# main_schematic.net
KiCad netlist of a schematic drawn in Altium Designer
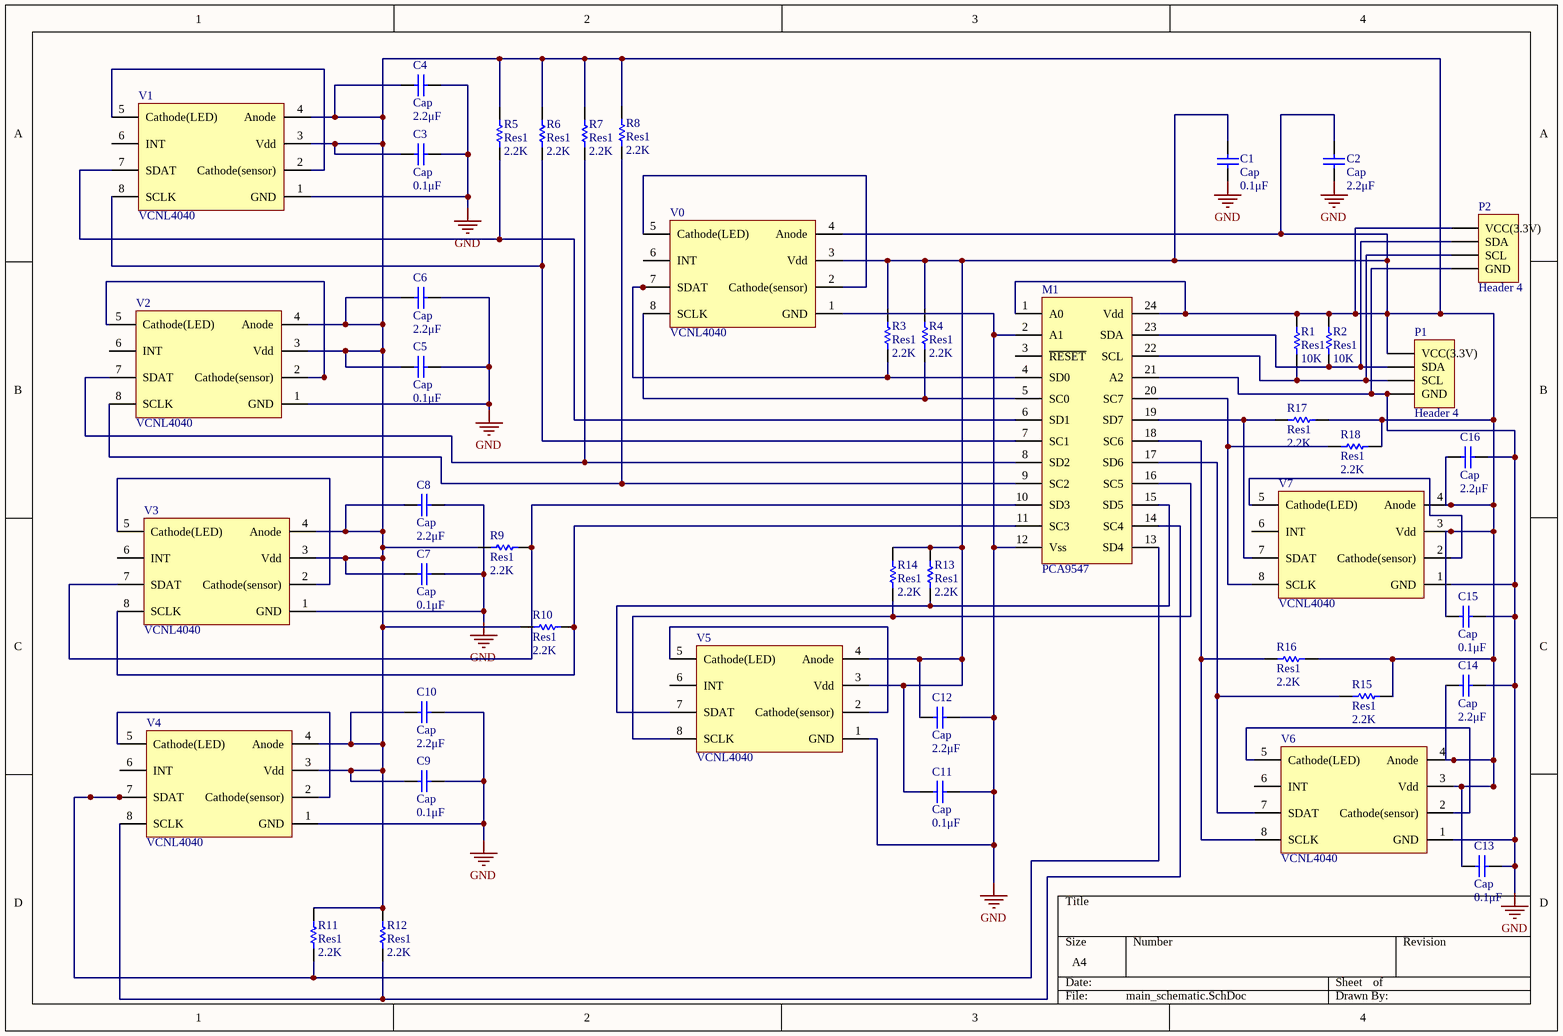
[diagram p0: main_schematic.SchDoc]

(export (version "E")
  (design (tool "Eeschema 10.0.6"))
  (components
    (comp (ref "C1")
      (value "Cap")
      (footprint "1608[0603]")
      (description "Capacitor")
      (fields (field (name "ALTIUM_VALUE") "0.1μF") (field (name "PUBLISHER") "Altium Limited"))
      (libsource (lib "Miscellaneous Devices") (part "Cap"))
    )
    (comp (ref "C2")
      (value "Cap")
      (footprint "1608[0603]")
      (description "Capacitor")
      (fields (field (name "ALTIUM_VALUE") "2.2μF") (field (name "PUBLISHER") "Altium Limited"))
      (libsource (lib "Miscellaneous Devices") (part "Cap"))
    )
    (comp (ref "C3")
      (value "Cap")
      (footprint "1608[0603]")
      (description "Capacitor")
      (fields (field (name "ALTIUM_VALUE") "0.1μF") (field (name "PUBLISHER") "Altium Limited"))
      (libsource (lib "Miscellaneous Devices") (part "Cap"))
    )
    (comp (ref "C4")
      (value "Cap")
      (footprint "1608[0603]")
      (description "Capacitor")
      (fields (field (name "ALTIUM_VALUE") "2.2μF") (field (name "PUBLISHER") "Altium Limited"))
      (libsource (lib "Miscellaneous Devices") (part "Cap"))
    )
    (comp (ref "C5")
      (value "Cap")
      (footprint "1608[0603]")
      (description "Capacitor")
      (fields (field (name "ALTIUM_VALUE") "0.1μF") (field (name "PUBLISHER") "Altium Limited"))
      (libsource (lib "Miscellaneous Devices") (part "Cap"))
    )
    (comp (ref "C6")
      (value "Cap")
      (footprint "1608[0603]")
      (description "Capacitor")
      (fields (field (name "ALTIUM_VALUE") "2.2μF") (field (name "PUBLISHER") "Altium Limited"))
      (libsource (lib "Miscellaneous Devices") (part "Cap"))
    )
    (comp (ref "C7")
      (value "Cap")
      (footprint "1608[0603]")
      (description "Capacitor")
      (fields (field (name "ALTIUM_VALUE") "0.1μF") (field (name "PUBLISHER") "Altium Limited"))
      (libsource (lib "Miscellaneous Devices") (part "Cap"))
    )
    (comp (ref "C8")
      (value "Cap")
      (footprint "1608[0603]")
      (description "Capacitor")
      (fields (field (name "ALTIUM_VALUE") "2.2μF") (field (name "PUBLISHER") "Altium Limited"))
      (libsource (lib "Miscellaneous Devices") (part "Cap"))
    )
    (comp (ref "C9")
      (value "Cap")
      (footprint "1608[0603]")
      (description "Capacitor")
      (fields (field (name "ALTIUM_VALUE") "0.1μF") (field (name "PUBLISHER") "Altium Limited"))
      (libsource (lib "Miscellaneous Devices") (part "Cap"))
    )
    (comp (ref "C10")
      (value "Cap")
      (footprint "1608[0603]")
      (description "Capacitor")
      (fields (field (name "ALTIUM_VALUE") "2.2μF") (field (name "PUBLISHER") "Altium Limited"))
      (libsource (lib "Miscellaneous Devices") (part "Cap"))
    )
    (comp (ref "C11")
      (value "Cap")
      (footprint "1608[0603]")
      (description "Capacitor")
      (fields (field (name "ALTIUM_VALUE") "0.1μF") (field (name "PUBLISHER") "Altium Limited"))
      (libsource (lib "Miscellaneous Devices") (part "Cap"))
    )
    (comp (ref "C12")
      (value "Cap")
      (footprint "1608[0603]")
      (description "Capacitor")
      (fields (field (name "ALTIUM_VALUE") "2.2μF") (field (name "PUBLISHER") "Altium Limited"))
      (libsource (lib "Miscellaneous Devices") (part "Cap"))
    )
    (comp (ref "C13")
      (value "Cap")
      (footprint "1608[0603]")
      (description "Capacitor")
      (fields (field (name "ALTIUM_VALUE") "0.1μF") (field (name "PUBLISHER") "Altium Limited"))
      (libsource (lib "Miscellaneous Devices") (part "Cap"))
    )
    (comp (ref "C14")
      (value "Cap")
      (footprint "1608[0603]")
      (description "Capacitor")
      (fields (field (name "ALTIUM_VALUE") "2.2μF") (field (name "PUBLISHER") "Altium Limited"))
      (libsource (lib "Miscellaneous Devices") (part "Cap"))
    )
    (comp (ref "C15")
      (value "Cap")
      (footprint "1608[0603]")
      (description "Capacitor")
      (fields (field (name "ALTIUM_VALUE") "0.1μF") (field (name "PUBLISHER") "Altium Limited"))
      (libsource (lib "Miscellaneous Devices") (part "Cap"))
    )
    (comp (ref "C16")
      (value "Cap")
      (footprint "1608[0603]")
      (description "Capacitor")
      (fields (field (name "ALTIUM_VALUE") "2.2μF") (field (name "PUBLISHER") "Altium Limited"))
      (libsource (lib "Miscellaneous Devices") (part "Cap"))
    )
    (comp (ref "M1") (value "PCA9547") (footprint "TSSOP24") (libsource (lib "PCA9547") (part "PCA9547")))
    (comp (ref "P1")
      (value "Header 4")
      (footprint "HDR1X4")
      (description "Header, 4-Pin")
      (fields (field (name "PUBLISHER") "Altium Limited"))
      (libsource (lib "Miscellaneous Connectors") (part "Header 4"))
    )
    (comp (ref "P2")
      (value "Header 4")
      (footprint "HDR1X4")
      (description "Header, 4-Pin")
      (fields (field (name "PUBLISHER") "Altium Limited"))
      (libsource (lib "Miscellaneous Connectors") (part "Header 4"))
    )
    (comp (ref "R1")
      (value "Res1")
      (footprint "1608[0603]")
      (description "Resistor")
      (fields (field (name "ALTIUM_VALUE") "10K") (field (name "PUBLISHER") "Altium Limited"))
      (libsource (lib "Miscellaneous Devices") (part "Res1"))
    )
    (comp (ref "R2")
      (value "Res1")
      (footprint "1608[0603]")
      (description "Resistor")
      (fields (field (name "ALTIUM_VALUE") "10K") (field (name "PUBLISHER") "Altium Limited"))
      (libsource (lib "Miscellaneous Devices") (part "Res1"))
    )
    (comp (ref "R3")
      (value "Res1")
      (footprint "1608[0603]")
      (description "Resistor")
      (fields (field (name "ALTIUM_VALUE") "2.2K") (field (name "PUBLISHER") "Altium Limited"))
      (libsource (lib "Miscellaneous Devices") (part "Res1"))
    )
    (comp (ref "R4")
      (value "Res1")
      (footprint "1608[0603]")
      (description "Resistor")
      (fields (field (name "ALTIUM_VALUE") "2.2K") (field (name "PUBLISHER") "Altium Limited"))
      (libsource (lib "Miscellaneous Devices") (part "Res1"))
    )
    (comp (ref "R5")
      (value "Res1")
      (footprint "1608[0603]")
      (description "Resistor")
      (fields (field (name "ALTIUM_VALUE") "2.2K") (field (name "PUBLISHER") "Altium Limited"))
      (libsource (lib "Miscellaneous Devices") (part "Res1"))
    )
    (comp (ref "R6")
      (value "Res1")
      (footprint "1608[0603]")
      (description "Resistor")
      (fields (field (name "ALTIUM_VALUE") "2.2K") (field (name "PUBLISHER") "Altium Limited"))
      (libsource (lib "Miscellaneous Devices") (part "Res1"))
    )
    (comp (ref "R7")
      (value "Res1")
      (footprint "1608[0603]")
      (description "Resistor")
      (fields (field (name "ALTIUM_VALUE") "2.2K") (field (name "PUBLISHER") "Altium Limited"))
      (libsource (lib "Miscellaneous Devices") (part "Res1"))
    )
    (comp (ref "R8")
      (value "Res1")
      (footprint "1608[0603]")
      (description "Resistor")
      (fields (field (name "ALTIUM_VALUE") "2.2K") (field (name "PUBLISHER") "Altium Limited"))
      (libsource (lib "Miscellaneous Devices") (part "Res1"))
    )
    (comp (ref "R9")
      (value "Res1")
      (footprint "1608[0603]")
      (description "Resistor")
      (fields (field (name "ALTIUM_VALUE") "2.2K") (field (name "PUBLISHER") "Altium Limited"))
      (libsource (lib "Miscellaneous Devices") (part "Res1"))
    )
    (comp (ref "R10")
      (value "Res1")
      (footprint "1608[0603]")
      (description "Resistor")
      (fields (field (name "ALTIUM_VALUE") "2.2K") (field (name "PUBLISHER") "Altium Limited"))
      (libsource (lib "Miscellaneous Devices") (part "Res1"))
    )
    (comp (ref "R11")
      (value "Res1")
      (footprint "1608[0603]")
      (description "Resistor")
      (fields (field (name "ALTIUM_VALUE") "2.2K") (field (name "PUBLISHER") "Altium Limited"))
      (libsource (lib "Miscellaneous Devices") (part "Res1"))
    )
    (comp (ref "R12")
      (value "Res1")
      (footprint "1608[0603]")
      (description "Resistor")
      (fields (field (name "ALTIUM_VALUE") "2.2K") (field (name "PUBLISHER") "Altium Limited"))
      (libsource (lib "Miscellaneous Devices") (part "Res1"))
    )
    (comp (ref "R13")
      (value "Res1")
      (footprint "1608[0603]")
      (description "Resistor")
      (fields (field (name "ALTIUM_VALUE") "2.2K") (field (name "PUBLISHER") "Altium Limited"))
      (libsource (lib "Miscellaneous Devices") (part "Res1"))
    )
    (comp (ref "R14")
      (value "Res1")
      (footprint "1608[0603]")
      (description "Resistor")
      (fields (field (name "ALTIUM_VALUE") "2.2K") (field (name "PUBLISHER") "Altium Limited"))
      (libsource (lib "Miscellaneous Devices") (part "Res1"))
    )
    (comp (ref "R15")
      (value "Res1")
      (footprint "1608[0603]")
      (description "Resistor")
      (fields (field (name "ALTIUM_VALUE") "2.2K") (field (name "PUBLISHER") "Altium Limited"))
      (libsource (lib "Miscellaneous Devices") (part "Res1"))
    )
    (comp (ref "R16")
      (value "Res1")
      (footprint "1608[0603]")
      (description "Resistor")
      (fields (field (name "ALTIUM_VALUE") "2.2K") (field (name "PUBLISHER") "Altium Limited"))
      (libsource (lib "Miscellaneous Devices") (part "Res1"))
    )
    (comp (ref "R17")
      (value "Res1")
      (footprint "1608[0603]")
      (description "Resistor")
      (fields (field (name "ALTIUM_VALUE") "2.2K") (field (name "PUBLISHER") "Altium Limited"))
      (libsource (lib "Miscellaneous Devices") (part "Res1"))
    )
    (comp (ref "R18")
      (value "Res1")
      (footprint "1608[0603]")
      (description "Resistor")
      (fields (field (name "ALTIUM_VALUE") "2.2K") (field (name "PUBLISHER") "Altium Limited"))
      (libsource (lib "Miscellaneous Devices") (part "Res1"))
    )
    (comp (ref "V0") (value "VCNL4040") (footprint "SOP8") (libsource (lib "VCNL4040") (part "Component_1")))
    (comp (ref "V1") (value "VCNL4040") (footprint "SOP8") (libsource (lib "VCNL4040") (part "Component_1")))
    (comp (ref "V2") (value "VCNL4040") (footprint "SOP8") (libsource (lib "VCNL4040") (part "Component_1")))
    (comp (ref "V3") (value "VCNL4040") (footprint "SOP8") (libsource (lib "VCNL4040") (part "Component_1")))
    (comp (ref "V4") (value "VCNL4040") (footprint "SOP8") (libsource (lib "VCNL4040") (part "Component_1")))
    (comp (ref "V5") (value "VCNL4040") (footprint "SOP8") (libsource (lib "VCNL4040") (part "Component_1")))
    (comp (ref "V6") (value "VCNL4040") (footprint "SOP8") (libsource (lib "VCNL4040") (part "Component_1")))
    (comp (ref "V7") (value "VCNL4040") (footprint "SOP8") (libsource (lib "VCNL4040") (part "Component_1")))
  )
  (nets
    (net (code "1") (name "GND") (class "Default")
      (node (ref "C1") (pin "1") (pinfunction "1_1") (pintype "passive"))
      (node (ref "C10") (pin "1") (pinfunction "1_1") (pintype "passive"))
      (node (ref "C11") (pin "1") (pinfunction "1_1") (pintype "passive"))
      (node (ref "C12") (pin "1") (pinfunction "1_1") (pintype "passive"))
      (node (ref "C13") (pin "1") (pinfunction "1_1") (pintype "passive"))
      (node (ref "C14") (pin "1") (pinfunction "1_1") (pintype "passive"))
      (node (ref "C15") (pin "1") (pinfunction "1_1") (pintype "passive"))
      (node (ref "C16") (pin "1") (pinfunction "1_1") (pintype "passive"))
      (node (ref "C2") (pin "1") (pinfunction "1_1") (pintype "passive"))
      (node (ref "C3") (pin "1") (pinfunction "1_1") (pintype "passive"))
      (node (ref "C4") (pin "1") (pinfunction "1_1") (pintype "passive"))
      (node (ref "C5") (pin "1") (pinfunction "1_1") (pintype "passive"))
      (node (ref "C6") (pin "1") (pinfunction "1_1") (pintype "passive"))
      (node (ref "C7") (pin "1") (pinfunction "1_1") (pintype "passive"))
      (node (ref "C8") (pin "1") (pinfunction "1_1") (pintype "passive"))
      (node (ref "C9") (pin "1") (pinfunction "1_1") (pintype "passive"))
      (node (ref "M1") (pin "12") (pinfunction "Vss_12") (pintype "passive"))
      (node (ref "M1") (pin "2") (pinfunction "A1_2") (pintype "passive"))
      (node (ref "M1") (pin "21") (pinfunction "A2_21") (pintype "passive"))
      (node (ref "P1") (pin "4") (pinfunction "GND_4") (pintype "passive"))
      (node (ref "P2") (pin "4") (pinfunction "GND_4") (pintype "passive"))
      (node (ref "V0") (pin "1") (pinfunction "GND_1") (pintype "passive"))
      (node (ref "V1") (pin "1") (pinfunction "GND_1") (pintype "passive"))
      (node (ref "V2") (pin "1") (pinfunction "GND_1") (pintype "passive"))
      (node (ref "V3") (pin "1") (pinfunction "GND_1") (pintype "passive"))
      (node (ref "V4") (pin "1") (pinfunction "GND_1") (pintype "passive"))
      (node (ref "V5") (pin "1") (pinfunction "GND_1") (pintype "passive"))
      (node (ref "V6") (pin "1") (pinfunction "GND_1") (pintype "passive"))
      (node (ref "V7") (pin "1") (pinfunction "GND_1") (pintype "passive"))
    )
    (net (code "2") (name "Net-(M1-A0)") (class "Default")
      (node (ref "C1") (pin "2") (pinfunction "2_2") (pintype "passive"))
      (node (ref "C10") (pin "2") (pinfunction "2_2") (pintype "passive"))
      (node (ref "C11") (pin "2") (pinfunction "2_2") (pintype "passive"))
      (node (ref "C12") (pin "2") (pinfunction "2_2") (pintype "passive"))
      (node (ref "C13") (pin "2") (pinfunction "2_2") (pintype "passive"))
      (node (ref "C14") (pin "2") (pinfunction "2_2") (pintype "passive"))
      (node (ref "C15") (pin "2") (pinfunction "2_2") (pintype "passive"))
      (node (ref "C16") (pin "2") (pinfunction "2_2") (pintype "passive"))
      (node (ref "C2") (pin "2") (pinfunction "2_2") (pintype "passive"))
      (node (ref "C3") (pin "2") (pinfunction "2_2") (pintype "passive"))
      (node (ref "C4") (pin "2") (pinfunction "2_2") (pintype "passive"))
      (node (ref "C5") (pin "2") (pinfunction "2_2") (pintype "passive"))
      (node (ref "C6") (pin "2") (pinfunction "2_2") (pintype "passive"))
      (node (ref "C7") (pin "2") (pinfunction "2_2") (pintype "passive"))
      (node (ref "C8") (pin "2") (pinfunction "2_2") (pintype "passive"))
      (node (ref "C9") (pin "2") (pinfunction "2_2") (pintype "passive"))
      (node (ref "M1") (pin "1") (pinfunction "A0_1") (pintype "passive"))
      (node (ref "M1") (pin "24") (pinfunction "Vdd_24") (pintype "passive"))
      (node (ref "P1") (pin "1") (pinfunction "VCC(3.3V)_1") (pintype "passive"))
      (node (ref "P2") (pin "1") (pinfunction "VCC(3.3V)_1") (pintype "passive"))
      (node (ref "R1") (pin "2") (pinfunction "2_2") (pintype "passive"))
      (node (ref "R10") (pin "2") (pinfunction "2_2") (pintype "passive"))
      (node (ref "R11") (pin "1") (pinfunction "1_1") (pintype "passive"))
      (node (ref "R12") (pin "1") (pinfunction "1_1") (pintype "passive"))
      (node (ref "R13") (pin "2") (pinfunction "2_2") (pintype "passive"))
      (node (ref "R14") (pin "2") (pinfunction "2_2") (pintype "passive"))
      (node (ref "R15") (pin "1") (pinfunction "1_1") (pintype "passive"))
      (node (ref "R16") (pin "1") (pinfunction "1_1") (pintype "passive"))
      (node (ref "R17") (pin "1") (pinfunction "1_1") (pintype "passive"))
      (node (ref "R18") (pin "1") (pinfunction "1_1") (pintype "passive"))
      (node (ref "R2") (pin "2") (pinfunction "2_2") (pintype "passive"))
      (node (ref "R3") (pin "2") (pinfunction "2_2") (pintype "passive"))
      (node (ref "R4") (pin "2") (pinfunction "2_2") (pintype "passive"))
      (node (ref "R5") (pin "2") (pinfunction "2_2") (pintype "passive"))
      (node (ref "R6") (pin "2") (pinfunction "2_2") (pintype "passive"))
      (node (ref "R7") (pin "2") (pinfunction "2_2") (pintype "passive"))
      (node (ref "R8") (pin "2") (pinfunction "2_2") (pintype "passive"))
      (node (ref "R9") (pin "2") (pinfunction "2_2") (pintype "passive"))
      (node (ref "V0") (pin "3") (pinfunction "Vdd_3") (pintype "passive"))
      (node (ref "V0") (pin "4") (pinfunction "Anode_4") (pintype "passive"))
      (node (ref "V1") (pin "3") (pinfunction "Vdd_3") (pintype "passive"))
      (node (ref "V1") (pin "4") (pinfunction "Anode_4") (pintype "passive"))
      (node (ref "V2") (pin "3") (pinfunction "Vdd_3") (pintype "passive"))
      (node (ref "V2") (pin "4") (pinfunction "Anode_4") (pintype "passive"))
      (node (ref "V3") (pin "3") (pinfunction "Vdd_3") (pintype "passive"))
      (node (ref "V3") (pin "4") (pinfunction "Anode_4") (pintype "passive"))
      (node (ref "V4") (pin "3") (pinfunction "Vdd_3") (pintype "passive"))
      (node (ref "V4") (pin "4") (pinfunction "Anode_4") (pintype "passive"))
      (node (ref "V5") (pin "3") (pinfunction "Vdd_3") (pintype "passive"))
      (node (ref "V5") (pin "4") (pinfunction "Anode_4") (pintype "passive"))
      (node (ref "V6") (pin "3") (pinfunction "Vdd_3") (pintype "passive"))
      (node (ref "V6") (pin "4") (pinfunction "Anode_4") (pintype "passive"))
      (node (ref "V7") (pin "3") (pinfunction "Vdd_3") (pintype "passive"))
      (node (ref "V7") (pin "4") (pinfunction "Anode_4") (pintype "passive"))
    )
    (net (code "3") (name "Net-(M1-SC0)") (class "Default")
      (node (ref "M1") (pin "5") (pinfunction "SC0_5") (pintype "passive"))
      (node (ref "R4") (pin "1") (pinfunction "1_1") (pintype "passive"))
      (node (ref "V0") (pin "8") (pinfunction "SCLK_8") (pintype "passive"))
    )
    (net (code "4") (name "Net-(M1-SC1)") (class "Default")
      (node (ref "M1") (pin "7") (pinfunction "SC1_7") (pintype "passive"))
      (node (ref "R6") (pin "1") (pinfunction "1_1") (pintype "passive"))
      (node (ref "V1") (pin "8") (pinfunction "SCLK_8") (pintype "passive"))
    )
    (net (code "5") (name "Net-(M1-SC2)") (class "Default")
      (node (ref "M1") (pin "9") (pinfunction "SC2_9") (pintype "passive"))
      (node (ref "R8") (pin "1") (pinfunction "1_1") (pintype "passive"))
      (node (ref "V2") (pin "8") (pinfunction "SCLK_8") (pintype "passive"))
    )
    (net (code "6") (name "Net-(M1-SC3)") (class "Default")
      (node (ref "M1") (pin "11") (pinfunction "SC3_11") (pintype "passive"))
      (node (ref "R10") (pin "1") (pinfunction "1_1") (pintype "passive"))
      (node (ref "V3") (pin "8") (pinfunction "SCLK_8") (pintype "passive"))
    )
    (net (code "7") (name "Net-(M1-SC4)") (class "Default")
      (node (ref "M1") (pin "14") (pinfunction "SC4_14") (pintype "passive"))
      (node (ref "R12") (pin "2") (pinfunction "2_2") (pintype "passive"))
      (node (ref "V4") (pin "8") (pinfunction "SCLK_8") (pintype "passive"))
    )
    (net (code "8") (name "Net-(M1-SC5)") (class "Default")
      (node (ref "M1") (pin "16") (pinfunction "SC5_16") (pintype "passive"))
      (node (ref "R14") (pin "1") (pinfunction "1_1") (pintype "passive"))
      (node (ref "V5") (pin "8") (pinfunction "SCLK_8") (pintype "passive"))
    )
    (net (code "9") (name "Net-(M1-SC6)") (class "Default")
      (node (ref "M1") (pin "18") (pinfunction "SC6_18") (pintype "passive"))
      (node (ref "R16") (pin "2") (pinfunction "2_2") (pintype "passive"))
      (node (ref "V6") (pin "8") (pinfunction "SCLK_8") (pintype "passive"))
    )
    (net (code "10") (name "Net-(M1-SC7)") (class "Default")
      (node (ref "M1") (pin "20") (pinfunction "SC7_20") (pintype "passive"))
      (node (ref "R18") (pin "2") (pinfunction "2_2") (pintype "passive"))
      (node (ref "V7") (pin "8") (pinfunction "SCLK_8") (pintype "passive"))
    )
    (net (code "11") (name "Net-(M1-SCL)") (class "Default")
      (node (ref "M1") (pin "22") (pinfunction "SCL_22") (pintype "passive"))
      (node (ref "P1") (pin "3") (pinfunction "SCL_3") (pintype "passive"))
      (node (ref "P2") (pin "3") (pinfunction "SCL_3") (pintype "passive"))
      (node (ref "R1") (pin "1") (pinfunction "1_1") (pintype "passive"))
    )
    (net (code "12") (name "Net-(M1-SD0)") (class "Default")
      (node (ref "M1") (pin "4") (pinfunction "SD0_4") (pintype "passive"))
      (node (ref "R3") (pin "1") (pinfunction "1_1") (pintype "passive"))
      (node (ref "V0") (pin "7") (pinfunction "SDAT_7") (pintype "passive"))
    )
    (net (code "13") (name "Net-(M1-SD1)") (class "Default")
      (node (ref "M1") (pin "6") (pinfunction "SD1_6") (pintype "passive"))
      (node (ref "R5") (pin "1") (pinfunction "1_1") (pintype "passive"))
      (node (ref "V1") (pin "7") (pinfunction "SDAT_7") (pintype "passive"))
    )
    (net (code "14") (name "Net-(M1-SD2)") (class "Default")
      (node (ref "M1") (pin "8") (pinfunction "SD2_8") (pintype "passive"))
      (node (ref "R7") (pin "1") (pinfunction "1_1") (pintype "passive"))
      (node (ref "V2") (pin "7") (pinfunction "SDAT_7") (pintype "passive"))
    )
    (net (code "15") (name "Net-(M1-SD3)") (class "Default")
      (node (ref "M1") (pin "10") (pinfunction "SD3_10") (pintype "passive"))
      (node (ref "R9") (pin "1") (pinfunction "1_1") (pintype "passive"))
      (node (ref "V3") (pin "7") (pinfunction "SDAT_7") (pintype "passive"))
    )
    (net (code "16") (name "Net-(M1-SD4)") (class "Default")
      (node (ref "M1") (pin "13") (pinfunction "SD4_13") (pintype "passive"))
      (node (ref "R11") (pin "2") (pinfunction "2_2") (pintype "passive"))
      (node (ref "V4") (pin "7") (pinfunction "SDAT_7") (pintype "passive"))
    )
    (net (code "17") (name "Net-(M1-SD5)") (class "Default")
      (node (ref "M1") (pin "15") (pinfunction "SD5_15") (pintype "passive"))
      (node (ref "R13") (pin "1") (pinfunction "1_1") (pintype "passive"))
      (node (ref "V5") (pin "7") (pinfunction "SDAT_7") (pintype "passive"))
    )
    (net (code "18") (name "Net-(M1-SD6)") (class "Default")
      (node (ref "M1") (pin "17") (pinfunction "SD6_17") (pintype "passive"))
      (node (ref "R15") (pin "2") (pinfunction "2_2") (pintype "passive"))
      (node (ref "V6") (pin "7") (pinfunction "SDAT_7") (pintype "passive"))
    )
    (net (code "19") (name "Net-(M1-SD7)") (class "Default")
      (node (ref "M1") (pin "19") (pinfunction "SD7_19") (pintype "passive"))
      (node (ref "R17") (pin "2") (pinfunction "2_2") (pintype "passive"))
      (node (ref "V7") (pin "7") (pinfunction "SDAT_7") (pintype "passive"))
    )
    (net (code "20") (name "Net-(M1-SDA)") (class "Default")
      (node (ref "M1") (pin "23") (pinfunction "SDA_23") (pintype "passive"))
      (node (ref "P1") (pin "2") (pinfunction "SDA_2") (pintype "passive"))
      (node (ref "P2") (pin "2") (pinfunction "SDA_2") (pintype "passive"))
      (node (ref "R2") (pin "1") (pinfunction "1_1") (pintype "passive"))
    )
    (net (code "21") (name "Net-(V0-Cathode(LED))") (class "Default")
      (node (ref "V0") (pin "2") (pinfunction "Cathode(sensor)_2") (pintype "passive"))
      (node (ref "V0") (pin "5") (pinfunction "Cathode(LED)_5") (pintype "passive"))
    )
    (net (code "22") (name "Net-(V1-Cathode(LED))") (class "Default")
      (node (ref "V1") (pin "2") (pinfunction "Cathode(sensor)_2") (pintype "passive"))
      (node (ref "V1") (pin "5") (pinfunction "Cathode(LED)_5") (pintype "passive"))
    )
    (net (code "23") (name "Net-(V2-Cathode(LED))") (class "Default")
      (node (ref "V2") (pin "2") (pinfunction "Cathode(sensor)_2") (pintype "passive"))
      (node (ref "V2") (pin "5") (pinfunction "Cathode(LED)_5") (pintype "passive"))
    )
    (net (code "24") (name "Net-(V3-Cathode(LED))") (class "Default")
      (node (ref "V3") (pin "2") (pinfunction "Cathode(sensor)_2") (pintype "passive"))
      (node (ref "V3") (pin "5") (pinfunction "Cathode(LED)_5") (pintype "passive"))
    )
    (net (code "25") (name "Net-(V4-Cathode(LED))") (class "Default")
      (node (ref "V4") (pin "2") (pinfunction "Cathode(sensor)_2") (pintype "passive"))
      (node (ref "V4") (pin "5") (pinfunction "Cathode(LED)_5") (pintype "passive"))
    )
    (net (code "26") (name "Net-(V5-Cathode(LED))") (class "Default")
      (node (ref "V5") (pin "2") (pinfunction "Cathode(sensor)_2") (pintype "passive"))
      (node (ref "V5") (pin "5") (pinfunction "Cathode(LED)_5") (pintype "passive"))
    )
    (net (code "27") (name "Net-(V6-Cathode(LED))") (class "Default")
      (node (ref "V6") (pin "2") (pinfunction "Cathode(sensor)_2") (pintype "passive"))
      (node (ref "V6") (pin "5") (pinfunction "Cathode(LED)_5") (pintype "passive"))
    )
    (net (code "28") (name "Net-(V7-Cathode(LED))") (class "Default")
      (node (ref "V7") (pin "2") (pinfunction "Cathode(sensor)_2") (pintype "passive"))
      (node (ref "V7") (pin "5") (pinfunction "Cathode(LED)_5") (pintype "passive"))
    )
    (net (code "29") (name "unconnected-(M1-~{RESET}-Pad3)") (class "Default")
      (node (ref "M1") (pin "3") (pinfunction "~{RESET}_3") (pintype "passive"))
    )
    (net (code "30") (name "unconnected-(V0-INT-Pad6)") (class "Default")
      (node (ref "V0") (pin "6") (pinfunction "INT_6") (pintype "passive"))
    )
    (net (code "31") (name "unconnected-(V1-INT-Pad6)") (class "Default")
      (node (ref "V1") (pin "6") (pinfunction "INT_6") (pintype "passive"))
    )
    (net (code "32") (name "unconnected-(V2-INT-Pad6)") (class "Default")
      (node (ref "V2") (pin "6") (pinfunction "INT_6") (pintype "passive"))
    )
    (net (code "33") (name "unconnected-(V3-INT-Pad6)") (class "Default")
      (node (ref "V3") (pin "6") (pinfunction "INT_6") (pintype "passive"))
    )
    (net (code "34") (name "unconnected-(V4-INT-Pad6)") (class "Default")
      (node (ref "V4") (pin "6") (pinfunction "INT_6") (pintype "passive"))
    )
    (net (code "35") (name "unconnected-(V5-INT-Pad6)") (class "Default")
      (node (ref "V5") (pin "6") (pinfunction "INT_6") (pintype "passive"))
    )
    (net (code "36") (name "unconnected-(V6-INT-Pad6)") (class "Default")
      (node (ref "V6") (pin "6") (pinfunction "INT_6") (pintype "passive"))
    )
    (net (code "37") (name "unconnected-(V7-INT-Pad6)") (class "Default")
      (node (ref "V7") (pin "6") (pinfunction "INT_6") (pintype "passive"))
    )
  )
)
